# 780-00012-P3_Sch_M2_Focus_Drive.net
KiCad netlist of a schematic drawn in Altium Designer
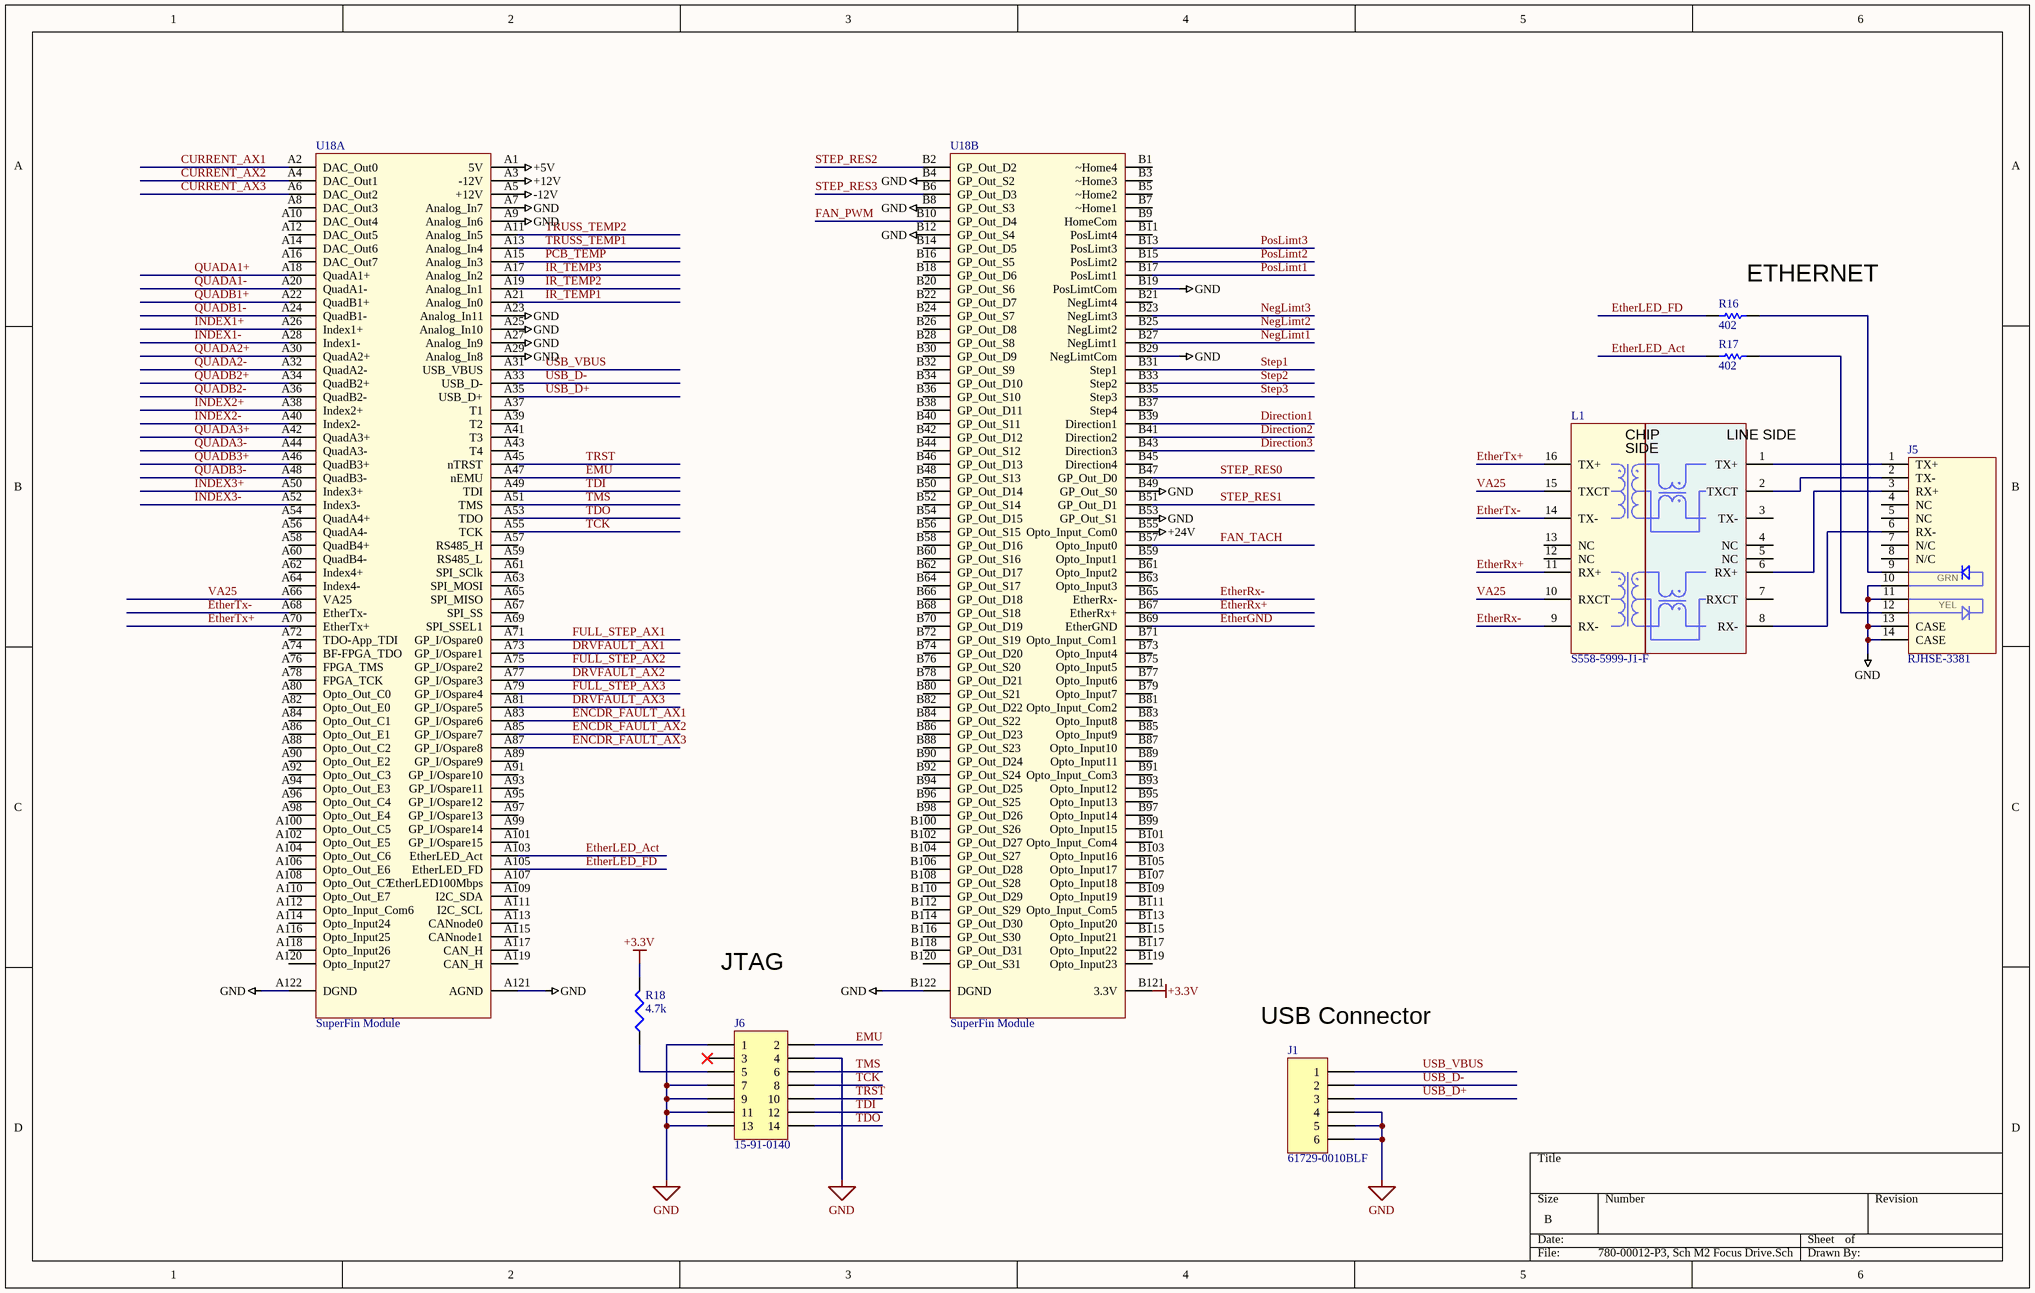
[diagram p0: 780-00012-P3, Sch M2 Focus Drive.SchDoc]

(export (version "E")
  (design (tool "Eeschema 10.0.6"))
  (components
    (comp (ref "J1")
      (value "61729-0010BLF")
      (footprint "USB Vertical PCB")
      (description "Header, 6-Pin")
      (fields (field (name "MANUFACTURER") "FCI"))
      (libsource (lib "Miscellaneous Connectors") (part "Header 6"))
    )
    (comp (ref "J5")
      (value "RJHSE-3381")
      (footprint "RJ45, VERT MOUNT, NO MAGNETICS")
      (description "Vertical PC mount, w/o magnetics")
      (libsource (lib "Richs Schematic Components") (part "CONN RJ-45 w/o magnetics"))
    )
    (comp (ref "J6")
      (value "15-91-0140")
      (footprint "HDR2X7")
      (description "Header, 7-Pin, Dual row")
      (fields (field (name "MANUFACTURER") "Molex/Waldom"))
      (libsource (lib "Miscellaneous Connectors") (part "Header 7X2"))
    )
    (comp (ref "L1")
      (value "S558-5999-J1-F")
      (footprint "10/100BT Magetics module")
      (description "10/100BT Magnetics Module")
      (libsource (lib "Richs Schematic Components") (part "Ethernet Magnetics module"))
    )
    (comp (ref "R16")
      (value "402")
      (footprint "SMD_0805")
      (description "Resistor 0805")
      (fields (field (name "MANUFACTURER") "Vishay/Dale") (field (name "Comment") "Res 0805"))
      (libsource (lib "Richs Schematic Components") (part "Res SMD"))
    )
    (comp (ref "R17")
      (value "402")
      (footprint "SMD_0805")
      (description "Resistor 0805")
      (fields (field (name "MANUFACTURER") "Vishay/Dale") (field (name "Comment") "Res 0805"))
      (libsource (lib "Richs Schematic Components") (part "Res SMD"))
    )
    (comp (ref "R18")
      (value "4.7k")
      (footprint "2012[0805]")
      (description "Resistor")
      (fields (field (name "MANUFACTURER") "Dale/Vishay"))
      (libsource (lib "Miscellaneous Devices") (part "Res3"))
    )
    (comp (ref "U18")
      (value "SuperFin Module")
      (footprint "SuperFin Footprint")
      (libsource (lib "Richs Schematic Components") (part "SuperFin Module"))
    )
  )
  (nets
    (net (code "1") (name "+3.3V") (class "Default")
      (node (ref "R18") (pin "2") (pinfunction "2_2") (pintype "passive"))
      (node (ref "U18") (pin "B121") (pinfunction "3.3V_B121") (pintype "passive"))
    )
    (net (code "2") (name "+5V") (class "Default")
      (node (ref "U18") (pin "A1") (pinfunction "5V_A1") (pintype "passive"))
    )
    (net (code "3") (name "+12V") (class "Default")
      (node (ref "U18") (pin "A3") (pinfunction "-12V_A3") (pintype "passive"))
    )
    (net (code "4") (name "+24V") (class "Default")
      (node (ref "U18") (pin "B55") (pinfunction "Opto_Input_Com0_B55") (pintype "passive"))
    )
    (net (code "5") (name "-12V") (class "Default")
      (node (ref "U18") (pin "A5") (pinfunction "+12V_A5") (pintype "passive"))
    )
    (net (code "6") (name "/CURRENT_AX1") (class "Default")
      (node (ref "U18") (pin "A2") (pinfunction "DAC_Out0_A2") (pintype "passive"))
    )
    (net (code "7") (name "/CURRENT_AX2") (class "Default")
      (node (ref "U18") (pin "A4") (pinfunction "DAC_Out1_A4") (pintype "passive"))
    )
    (net (code "8") (name "/CURRENT_AX3") (class "Default")
      (node (ref "U18") (pin "A6") (pinfunction "DAC_Out2_A6") (pintype "passive"))
    )
    (net (code "9") (name "/DRVFAULT_AX1") (class "Default")
      (node (ref "U18") (pin "A73") (pinfunction "GP_I/Ospare1_A73") (pintype "passive"))
    )
    (net (code "10") (name "/DRVFAULT_AX2") (class "Default")
      (node (ref "U18") (pin "A77") (pinfunction "GP_I/Ospare3_A77") (pintype "passive"))
    )
    (net (code "11") (name "/DRVFAULT_AX3") (class "Default")
      (node (ref "U18") (pin "A81") (pinfunction "GP_I/Ospare5_A81") (pintype "passive"))
    )
    (net (code "12") (name "/Direction1") (class "Default")
      (node (ref "U18") (pin "B39") (pinfunction "Direction1_B39") (pintype "passive"))
    )
    (net (code "13") (name "/Direction2") (class "Default")
      (node (ref "U18") (pin "B41") (pinfunction "Direction2_B41") (pintype "passive"))
    )
    (net (code "14") (name "/Direction3") (class "Default")
      (node (ref "U18") (pin "B43") (pinfunction "Direction3_B43") (pintype "passive"))
    )
    (net (code "15") (name "/EMU") (class "Default")
      (node (ref "J6") (pin "2") (pinfunction "2_2") (pintype "passive"))
      (node (ref "U18") (pin "A47") (pinfunction "nEMU_A47") (pintype "passive"))
    )
    (net (code "16") (name "/ENCDR_FAULT_AX1") (class "Default")
      (node (ref "U18") (pin "A83") (pinfunction "GP_I/Ospare6_A83") (pintype "passive"))
    )
    (net (code "17") (name "/ENCDR_FAULT_AX2") (class "Default")
      (node (ref "U18") (pin "A85") (pinfunction "GP_I/Ospare7_A85") (pintype "passive"))
    )
    (net (code "18") (name "/ENCDR_FAULT_AX3") (class "Default")
      (node (ref "U18") (pin "A87") (pinfunction "GP_I/Ospare8_A87") (pintype "passive"))
    )
    (net (code "19") (name "/EtherGND") (class "Default")
      (node (ref "U18") (pin "B69") (pinfunction "EtherGND_B69") (pintype "passive"))
    )
    (net (code "20") (name "/EtherLED_Act") (class "Default")
      (node (ref "R17") (pin "1") (pinfunction "1_1") (pintype "passive"))
      (node (ref "U18") (pin "A103") (pinfunction "EtherLED_Act_A103") (pintype "passive"))
    )
    (net (code "21") (name "/EtherLED_FD") (class "Default")
      (node (ref "R16") (pin "1") (pinfunction "1_1") (pintype "passive"))
      (node (ref "U18") (pin "A105") (pinfunction "EtherLED_FD_A105") (pintype "passive"))
    )
    (net (code "22") (name "/EtherRx+") (class "Default")
      (node (ref "L1") (pin "11") (pinfunction "RX+_11") (pintype "passive"))
      (node (ref "U18") (pin "B67") (pinfunction "EtherRx+_B67") (pintype "passive"))
    )
    (net (code "23") (name "/EtherRx-") (class "Default")
      (node (ref "L1") (pin "9") (pinfunction "RX-_9") (pintype "passive"))
      (node (ref "U18") (pin "B65") (pinfunction "EtherRx-_B65") (pintype "passive"))
    )
    (net (code "24") (name "/EtherTx+") (class "Default")
      (node (ref "L1") (pin "16") (pinfunction "TX+_16") (pintype "passive"))
      (node (ref "U18") (pin "A70") (pinfunction "EtherTx+_A70") (pintype "passive"))
    )
    (net (code "25") (name "/EtherTx-") (class "Default")
      (node (ref "L1") (pin "14") (pinfunction "TX-_14") (pintype "passive"))
      (node (ref "U18") (pin "A68") (pinfunction "EtherTx-_A68") (pintype "passive"))
    )
    (net (code "26") (name "/FAN_PWM") (class "Default")
      (node (ref "U18") (pin "B10") (pinfunction "GP_Out_D4_B10") (pintype "passive"))
    )
    (net (code "27") (name "/FAN_TACH") (class "Default")
      (node (ref "U18") (pin "B57") (pinfunction "Opto_Input0_B57") (pintype "passive"))
    )
    (net (code "28") (name "/FULL_STEP_AX1") (class "Default")
      (node (ref "U18") (pin "A71") (pinfunction "GP_I/Ospare0_A71") (pintype "passive"))
    )
    (net (code "29") (name "/FULL_STEP_AX2") (class "Default")
      (node (ref "U18") (pin "A75") (pinfunction "GP_I/Ospare2_A75") (pintype "passive"))
    )
    (net (code "30") (name "/FULL_STEP_AX3") (class "Default")
      (node (ref "U18") (pin "A79") (pinfunction "GP_I/Ospare4_A79") (pintype "passive"))
    )
    (net (code "31") (name "/INDEX1+") (class "Default")
      (node (ref "U18") (pin "A26") (pinfunction "Index1+_A26") (pintype "passive"))
    )
    (net (code "32") (name "/INDEX1-") (class "Default")
      (node (ref "U18") (pin "A28") (pinfunction "Index1-_A28") (pintype "passive"))
    )
    (net (code "33") (name "/INDEX2+") (class "Default")
      (node (ref "U18") (pin "A38") (pinfunction "Index2+_A38") (pintype "passive"))
    )
    (net (code "34") (name "/INDEX2-") (class "Default")
      (node (ref "U18") (pin "A40") (pinfunction "Index2-_A40") (pintype "passive"))
    )
    (net (code "35") (name "/INDEX3+") (class "Default")
      (node (ref "U18") (pin "A50") (pinfunction "Index3+_A50") (pintype "passive"))
    )
    (net (code "36") (name "/INDEX3-") (class "Default")
      (node (ref "U18") (pin "A52") (pinfunction "Index3-_A52") (pintype "passive"))
    )
    (net (code "37") (name "/IR_TEMP1") (class "Default")
      (node (ref "U18") (pin "A21") (pinfunction "Analog_In0_A21") (pintype "passive"))
    )
    (net (code "38") (name "/IR_TEMP2") (class "Default")
      (node (ref "U18") (pin "A19") (pinfunction "Analog_In1_A19") (pintype "passive"))
    )
    (net (code "39") (name "/IR_TEMP3") (class "Default")
      (node (ref "U18") (pin "A17") (pinfunction "Analog_In2_A17") (pintype "passive"))
    )
    (net (code "40") (name "/NegLimt1") (class "Default")
      (node (ref "U18") (pin "B27") (pinfunction "NegLimt1_B27") (pintype "passive"))
    )
    (net (code "41") (name "/NegLimt2") (class "Default")
      (node (ref "U18") (pin "B25") (pinfunction "NegLimt2_B25") (pintype "passive"))
    )
    (net (code "42") (name "/NegLimt3") (class "Default")
      (node (ref "U18") (pin "B23") (pinfunction "NegLimt3_B23") (pintype "passive"))
    )
    (net (code "43") (name "/PCB_TEMP") (class "Default")
      (node (ref "U18") (pin "A15") (pinfunction "Analog_In3_A15") (pintype "passive"))
    )
    (net (code "44") (name "/PosLimt1") (class "Default")
      (node (ref "U18") (pin "B17") (pinfunction "PosLimt1_B17") (pintype "passive"))
    )
    (net (code "45") (name "/PosLimt2") (class "Default")
      (node (ref "U18") (pin "B15") (pinfunction "PosLimt2_B15") (pintype "passive"))
    )
    (net (code "46") (name "/PosLimt3") (class "Default")
      (node (ref "U18") (pin "B13") (pinfunction "PosLimt3_B13") (pintype "passive"))
    )
    (net (code "47") (name "/QUADA1+") (class "Default")
      (node (ref "U18") (pin "A18") (pinfunction "QuadA1+_A18") (pintype "passive"))
    )
    (net (code "48") (name "/QUADA1-") (class "Default")
      (node (ref "U18") (pin "A20") (pinfunction "QuadA1-_A20") (pintype "passive"))
    )
    (net (code "49") (name "/QUADA2+") (class "Default")
      (node (ref "U18") (pin "A30") (pinfunction "QuadA2+_A30") (pintype "passive"))
    )
    (net (code "50") (name "/QUADA2-") (class "Default")
      (node (ref "U18") (pin "A32") (pinfunction "QuadA2-_A32") (pintype "passive"))
    )
    (net (code "51") (name "/QUADA3+") (class "Default")
      (node (ref "U18") (pin "A42") (pinfunction "QuadA3+_A42") (pintype "passive"))
    )
    (net (code "52") (name "/QUADA3-") (class "Default")
      (node (ref "U18") (pin "A44") (pinfunction "QuadA3-_A44") (pintype "passive"))
    )
    (net (code "53") (name "/QUADB1+") (class "Default")
      (node (ref "U18") (pin "A22") (pinfunction "QuadB1+_A22") (pintype "passive"))
    )
    (net (code "54") (name "/QUADB1-") (class "Default")
      (node (ref "U18") (pin "A24") (pinfunction "QuadB1-_A24") (pintype "passive"))
    )
    (net (code "55") (name "/QUADB2+") (class "Default")
      (node (ref "U18") (pin "A34") (pinfunction "QuadB2+_A34") (pintype "passive"))
    )
    (net (code "56") (name "/QUADB2-") (class "Default")
      (node (ref "U18") (pin "A36") (pinfunction "QuadB2-_A36") (pintype "passive"))
    )
    (net (code "57") (name "/QUADB3+") (class "Default")
      (node (ref "U18") (pin "A46") (pinfunction "QuadB3+_A46") (pintype "passive"))
    )
    (net (code "58") (name "/QUADB3-") (class "Default")
      (node (ref "U18") (pin "A48") (pinfunction "QuadB3-_A48") (pintype "passive"))
    )
    (net (code "59") (name "/STEP_RES0") (class "Default")
      (node (ref "U18") (pin "B47") (pinfunction "GP_Out_D0_B47") (pintype "passive"))
    )
    (net (code "60") (name "/STEP_RES1") (class "Default")
      (node (ref "U18") (pin "B51") (pinfunction "GP_Out_D1_B51") (pintype "passive"))
    )
    (net (code "61") (name "/STEP_RES2") (class "Default")
      (node (ref "U18") (pin "B2") (pinfunction "GP_Out_D2_B2") (pintype "passive"))
    )
    (net (code "62") (name "/STEP_RES3") (class "Default")
      (node (ref "U18") (pin "B6") (pinfunction "GP_Out_D3_B6") (pintype "passive"))
    )
    (net (code "63") (name "/Step1") (class "Default")
      (node (ref "U18") (pin "B31") (pinfunction "Step1_B31") (pintype "passive"))
    )
    (net (code "64") (name "/Step2") (class "Default")
      (node (ref "U18") (pin "B33") (pinfunction "Step2_B33") (pintype "passive"))
    )
    (net (code "65") (name "/Step3") (class "Default")
      (node (ref "U18") (pin "B35") (pinfunction "Step3_B35") (pintype "passive"))
    )
    (net (code "66") (name "/TCK") (class "Default")
      (node (ref "J6") (pin "8") (pinfunction "8_8") (pintype "passive"))
      (node (ref "U18") (pin "A55") (pinfunction "TCK_A55") (pintype "passive"))
    )
    (net (code "67") (name "/TDI") (class "Default")
      (node (ref "J6") (pin "12") (pinfunction "12_12") (pintype "passive"))
      (node (ref "U18") (pin "A49") (pinfunction "TDI_A49") (pintype "passive"))
    )
    (net (code "68") (name "/TDO") (class "Default")
      (node (ref "J6") (pin "14") (pinfunction "14_14") (pintype "passive"))
      (node (ref "U18") (pin "A53") (pinfunction "TDO_A53") (pintype "passive"))
    )
    (net (code "69") (name "/TMS") (class "Default")
      (node (ref "J6") (pin "6") (pinfunction "6_6") (pintype "passive"))
      (node (ref "U18") (pin "A51") (pinfunction "TMS_A51") (pintype "passive"))
    )
    (net (code "70") (name "/TRST") (class "Default")
      (node (ref "J6") (pin "10") (pinfunction "10_10") (pintype "passive"))
      (node (ref "U18") (pin "A45") (pinfunction "nTRST_A45") (pintype "passive"))
    )
    (net (code "71") (name "/TRUSS_TEMP1") (class "Default")
      (node (ref "U18") (pin "A13") (pinfunction "Analog_In4_A13") (pintype "passive"))
    )
    (net (code "72") (name "/TRUSS_TEMP2") (class "Default")
      (node (ref "U18") (pin "A11") (pinfunction "Analog_In5_A11") (pintype "passive"))
    )
    (net (code "73") (name "/USB_D+") (class "Default")
      (node (ref "J1") (pin "3") (pinfunction "3_3") (pintype "passive"))
      (node (ref "U18") (pin "A35") (pinfunction "USB_D+_A35") (pintype "passive"))
    )
    (net (code "74") (name "/USB_D-") (class "Default")
      (node (ref "J1") (pin "2") (pinfunction "2_2") (pintype "passive"))
      (node (ref "U18") (pin "A33") (pinfunction "USB_D-_A33") (pintype "passive"))
    )
    (net (code "75") (name "/USB_VBUS") (class "Default")
      (node (ref "J1") (pin "1") (pinfunction "1_1") (pintype "passive"))
      (node (ref "U18") (pin "A31") (pinfunction "USB_VBUS_A31") (pintype "passive"))
    )
    (net (code "76") (name "/VA25") (class "Default")
      (node (ref "L1") (pin "10") (pinfunction "RXCT_10") (pintype "passive"))
      (node (ref "L1") (pin "15") (pinfunction "TXCT_15") (pintype "passive"))
      (node (ref "U18") (pin "A66") (pinfunction "VA25_A66") (pintype "passive"))
    )
    (net (code "77") (name "GND") (class "Default")
      (node (ref "J1") (pin "4") (pinfunction "4_4") (pintype "passive"))
      (node (ref "J1") (pin "5") (pinfunction "5_5") (pintype "passive"))
      (node (ref "J1") (pin "6") (pinfunction "6_6") (pintype "passive"))
      (node (ref "J5") (pin "10") (pinfunction "GRN-Cathode_10") (pintype "passive"))
      (node (ref "J5") (pin "11") (pinfunction "YEL-Cathode_11") (pintype "passive"))
      (node (ref "J5") (pin "13") (pinfunction "CASE_13") (pintype "passive"))
      (node (ref "J5") (pin "14") (pinfunction "CASE_14") (pintype "passive"))
      (node (ref "J6") (pin "1") (pinfunction "1_1") (pintype "passive"))
      (node (ref "J6") (pin "11") (pinfunction "11_11") (pintype "passive"))
      (node (ref "J6") (pin "13") (pinfunction "13_13") (pintype "passive"))
      (node (ref "J6") (pin "4") (pinfunction "4_4") (pintype "passive"))
      (node (ref "J6") (pin "7") (pinfunction "7_7") (pintype "passive"))
      (node (ref "J6") (pin "9") (pinfunction "9_9") (pintype "passive"))
      (node (ref "U18") (pin "A121") (pinfunction "AGND_A121") (pintype "passive"))
      (node (ref "U18") (pin "A122") (pinfunction "DGND_A122") (pintype "passive"))
      (node (ref "U18") (pin "A23") (pinfunction "Analog_In11_A23") (pintype "passive"))
      (node (ref "U18") (pin "A25") (pinfunction "Analog_In10_A25") (pintype "passive"))
      (node (ref "U18") (pin "A27") (pinfunction "Analog_In9_A27") (pintype "passive"))
      (node (ref "U18") (pin "A29") (pinfunction "Analog_In8_A29") (pintype "passive"))
      (node (ref "U18") (pin "A7") (pinfunction "Analog_In7_A7") (pintype "passive"))
      (node (ref "U18") (pin "A9") (pinfunction "Analog_In6_A9") (pintype "passive"))
      (node (ref "U18") (pin "B12") (pinfunction "GP_Out_S4_B12") (pintype "passive"))
      (node (ref "U18") (pin "B122") (pinfunction "DGND_B122") (pintype "passive"))
      (node (ref "U18") (pin "B19") (pinfunction "PosLimtCom_B19") (pintype "passive"))
      (node (ref "U18") (pin "B29") (pinfunction "NegLimtCom_B29") (pintype "passive"))
      (node (ref "U18") (pin "B4") (pinfunction "GP_Out_S2_B4") (pintype "passive"))
      (node (ref "U18") (pin "B49") (pinfunction "GP_Out_S0_B49") (pintype "passive"))
      (node (ref "U18") (pin "B53") (pinfunction "GP_Out_S1_B53") (pintype "passive"))
      (node (ref "U18") (pin "B8") (pinfunction "GP_Out_S3_B8") (pintype "passive"))
    )
    (net (code "78") (name "Net-(J5-GRN-Anode)") (class "Default")
      (node (ref "J5") (pin "9") (pinfunction "GRN-Anode_9") (pintype "passive"))
      (node (ref "R16") (pin "2") (pinfunction "2_2") (pintype "passive"))
    )
    (net (code "79") (name "Net-(J5-RX+)") (class "Default")
      (node (ref "J5") (pin "3") (pinfunction "RX+_3") (pintype "passive"))
      (node (ref "L1") (pin "6") (pinfunction "RX+_6") (pintype "passive"))
    )
    (net (code "80") (name "Net-(J5-RX-)") (class "Default")
      (node (ref "J5") (pin "6") (pinfunction "RX-_6") (pintype "passive"))
      (node (ref "L1") (pin "8") (pinfunction "RX-_8") (pintype "passive"))
    )
    (net (code "81") (name "Net-(J5-TX+)") (class "Default")
      (node (ref "J5") (pin "1") (pinfunction "TX+_1") (pintype "passive"))
      (node (ref "L1") (pin "1") (pinfunction "TX+_1") (pintype "passive"))
    )
    (net (code "82") (name "Net-(J5-TX-)") (class "Default")
      (node (ref "J5") (pin "2") (pinfunction "TX-_2") (pintype "passive"))
      (node (ref "L1") (pin "2") (pinfunction "TXCT_2") (pintype "passive"))
    )
    (net (code "83") (name "Net-(J5-YEL-Anode)") (class "Default")
      (node (ref "J5") (pin "12") (pinfunction "YEL-Anode_12") (pintype "passive"))
      (node (ref "R17") (pin "2") (pinfunction "2_2") (pintype "passive"))
    )
    (net (code "84") (name "Net-(J6-Pad5)") (class "Default")
      (node (ref "J6") (pin "5") (pinfunction "5_5") (pintype "passive"))
      (node (ref "R18") (pin "1") (pinfunction "1_1") (pintype "passive"))
    )
    (net (code "85") (name "unconnected-(J5-NC-Pad4)") (class "Default")
      (node (ref "J5") (pin "4") (pinfunction "NC_4") (pintype "passive"))
    )
    (net (code "86") (name "unconnected-(J5-NC-Pad5)") (class "Default")
      (node (ref "J5") (pin "5") (pinfunction "NC_5") (pintype "passive"))
    )
    (net (code "87") (name "unconnected-(J5-N{slash}C-Pad7)") (class "Default")
      (node (ref "J5") (pin "7") (pinfunction "N/C_7") (pintype "passive"))
    )
    (net (code "88") (name "unconnected-(J5-N{slash}C-Pad8)") (class "Default")
      (node (ref "J5") (pin "8") (pinfunction "N/C_8") (pintype "passive"))
    )
    (net (code "89") (name "unconnected-(J6-Pad3)") (class "Default")
      (node (ref "J6") (pin "3") (pinfunction "3_3") (pintype "passive+no_connect"))
    )
    (net (code "90") (name "unconnected-(L1-NC-Pad4)") (class "Default")
      (node (ref "L1") (pin "4") (pinfunction "NC_4") (pintype "passive"))
    )
    (net (code "91") (name "unconnected-(L1-NC-Pad5)") (class "Default")
      (node (ref "L1") (pin "5") (pinfunction "NC_5") (pintype "passive"))
    )
    (net (code "92") (name "unconnected-(L1-NC-Pad12)") (class "Default")
      (node (ref "L1") (pin "12") (pinfunction "NC_12") (pintype "passive"))
    )
    (net (code "93") (name "unconnected-(L1-NC-Pad13)") (class "Default")
      (node (ref "L1") (pin "13") (pinfunction "NC_13") (pintype "passive"))
    )
    (net (code "94") (name "unconnected-(L1-RXCT-Pad7)") (class "Default")
      (node (ref "L1") (pin "7") (pinfunction "RXCT_7") (pintype "passive"))
    )
    (net (code "95") (name "unconnected-(L1-TX--Pad3)") (class "Default")
      (node (ref "L1") (pin "3") (pinfunction "TX-_3") (pintype "passive"))
    )
    (net (code "96") (name "unconnected-(U18A-BF-FPGA_TDO-PadA74)") (class "Default")
      (node (ref "U18") (pin "A74") (pinfunction "BF-FPGA_TDO_A74") (pintype "passive"))
    )
    (net (code "97") (name "unconnected-(U18A-CAN_H-PadA117)") (class "Default")
      (node (ref "U18") (pin "A117") (pinfunction "CAN_H_A117") (pintype "passive"))
    )
    (net (code "98") (name "unconnected-(U18A-CAN_H-PadA119)") (class "Default")
      (node (ref "U18") (pin "A119") (pinfunction "CAN_H_A119") (pintype "passive"))
    )
    (net (code "99") (name "unconnected-(U18A-CANnode0-PadA113)") (class "Default")
      (node (ref "U18") (pin "A113") (pinfunction "CANnode0_A113") (pintype "passive"))
    )
    (net (code "100") (name "unconnected-(U18A-CANnode1-PadA115)") (class "Default")
      (node (ref "U18") (pin "A115") (pinfunction "CANnode1_A115") (pintype "passive"))
    )
    (net (code "101") (name "unconnected-(U18A-DAC_Out3-PadA8)") (class "Default")
      (node (ref "U18") (pin "A8") (pinfunction "DAC_Out3_A8") (pintype "passive"))
    )
    (net (code "102") (name "unconnected-(U18A-DAC_Out4-PadA10)") (class "Default")
      (node (ref "U18") (pin "A10") (pinfunction "DAC_Out4_A10") (pintype "passive"))
    )
    (net (code "103") (name "unconnected-(U18A-DAC_Out5-PadA12)") (class "Default")
      (node (ref "U18") (pin "A12") (pinfunction "DAC_Out5_A12") (pintype "passive"))
    )
    (net (code "104") (name "unconnected-(U18A-DAC_Out6-PadA14)") (class "Default")
      (node (ref "U18") (pin "A14") (pinfunction "DAC_Out6_A14") (pintype "passive"))
    )
    (net (code "105") (name "unconnected-(U18A-DAC_Out7-PadA16)") (class "Default")
      (node (ref "U18") (pin "A16") (pinfunction "DAC_Out7_A16") (pintype "passive"))
    )
    (net (code "106") (name "unconnected-(U18A-EtherLED100Mbps-PadA107)") (class "Default")
      (node (ref "U18") (pin "A107") (pinfunction "EtherLED100Mbps_A107") (pintype "passive"))
    )
    (net (code "107") (name "unconnected-(U18A-FPGA_TCK-PadA78)") (class "Default")
      (node (ref "U18") (pin "A78") (pinfunction "FPGA_TCK_A78") (pintype "passive"))
    )
    (net (code "108") (name "unconnected-(U18A-FPGA_TMS-PadA76)") (class "Default")
      (node (ref "U18") (pin "A76") (pinfunction "FPGA_TMS_A76") (pintype "passive"))
    )
    (net (code "109") (name "unconnected-(U18A-GP_I{slash}Ospare9-PadA89)") (class "Default")
      (node (ref "U18") (pin "A89") (pinfunction "GP_I/Ospare9_A89") (pintype "passive"))
    )
    (net (code "110") (name "unconnected-(U18A-GP_I{slash}Ospare10-PadA91)") (class "Default")
      (node (ref "U18") (pin "A91") (pinfunction "GP_I/Ospare10_A91") (pintype "passive"))
    )
    (net (code "111") (name "unconnected-(U18A-GP_I{slash}Ospare11-PadA93)") (class "Default")
      (node (ref "U18") (pin "A93") (pinfunction "GP_I/Ospare11_A93") (pintype "passive"))
    )
    (net (code "112") (name "unconnected-(U18A-GP_I{slash}Ospare12-PadA95)") (class "Default")
      (node (ref "U18") (pin "A95") (pinfunction "GP_I/Ospare12_A95") (pintype "passive"))
    )
    (net (code "113") (name "unconnected-(U18A-GP_I{slash}Ospare13-PadA97)") (class "Default")
      (node (ref "U18") (pin "A97") (pinfunction "GP_I/Ospare13_A97") (pintype "passive"))
    )
    (net (code "114") (name "unconnected-(U18A-GP_I{slash}Ospare14-PadA99)") (class "Default")
      (node (ref "U18") (pin "A99") (pinfunction "GP_I/Ospare14_A99") (pintype "passive"))
    )
    (net (code "115") (name "unconnected-(U18A-GP_I{slash}Ospare15-PadA101)") (class "Default")
      (node (ref "U18") (pin "A101") (pinfunction "GP_I/Ospare15_A101") (pintype "passive"))
    )
    (net (code "116") (name "unconnected-(U18A-I2C_SCL-PadA111)") (class "Default")
      (node (ref "U18") (pin "A111") (pinfunction "I2C_SCL_A111") (pintype "passive"))
    )
    (net (code "117") (name "unconnected-(U18A-I2C_SDA-PadA109)") (class "Default")
      (node (ref "U18") (pin "A109") (pinfunction "I2C_SDA_A109") (pintype "passive"))
    )
    (net (code "118") (name "unconnected-(U18A-Index4+-PadA62)") (class "Default")
      (node (ref "U18") (pin "A62") (pinfunction "Index4+_A62") (pintype "passive"))
    )
    (net (code "119") (name "unconnected-(U18A-Index4--PadA64)") (class "Default")
      (node (ref "U18") (pin "A64") (pinfunction "Index4-_A64") (pintype "passive"))
    )
    (net (code "120") (name "unconnected-(U18A-Opto_Input24-PadA114)") (class "Default")
      (node (ref "U18") (pin "A114") (pinfunction "Opto_Input24_A114") (pintype "passive"))
    )
    (net (code "121") (name "unconnected-(U18A-Opto_Input25-PadA116)") (class "Default")
      (node (ref "U18") (pin "A116") (pinfunction "Opto_Input25_A116") (pintype "passive"))
    )
    (net (code "122") (name "unconnected-(U18A-Opto_Input26-PadA118)") (class "Default")
      (node (ref "U18") (pin "A118") (pinfunction "Opto_Input26_A118") (pintype "passive"))
    )
    (net (code "123") (name "unconnected-(U18A-Opto_Input27-PadA120)") (class "Default")
      (node (ref "U18") (pin "A120") (pinfunction "Opto_Input27_A120") (pintype "passive"))
    )
    (net (code "124") (name "unconnected-(U18A-Opto_Input_Com6-PadA112)") (class "Default")
      (node (ref "U18") (pin "A112") (pinfunction "Opto_Input_Com6_A112") (pintype "passive"))
    )
    (net (code "125") (name "unconnected-(U18A-Opto_Out_C0-PadA80)") (class "Default")
      (node (ref "U18") (pin "A80") (pinfunction "Opto_Out_C0_A80") (pintype "passive"))
    )
    (net (code "126") (name "unconnected-(U18A-Opto_Out_C1-PadA84)") (class "Default")
      (node (ref "U18") (pin "A84") (pinfunction "Opto_Out_C1_A84") (pintype "passive"))
    )
    (net (code "127") (name "unconnected-(U18A-Opto_Out_C2-PadA88)") (class "Default")
      (node (ref "U18") (pin "A88") (pinfunction "Opto_Out_C2_A88") (pintype "passive"))
    )
    (net (code "128") (name "unconnected-(U18A-Opto_Out_C3-PadA92)") (class "Default")
      (node (ref "U18") (pin "A92") (pinfunction "Opto_Out_C3_A92") (pintype "passive"))
    )
    (net (code "129") (name "unconnected-(U18A-Opto_Out_C4-PadA96)") (class "Default")
      (node (ref "U18") (pin "A96") (pinfunction "Opto_Out_C4_A96") (pintype "passive"))
    )
    (net (code "130") (name "unconnected-(U18A-Opto_Out_C5-PadA100)") (class "Default")
      (node (ref "U18") (pin "A100") (pinfunction "Opto_Out_C5_A100") (pintype "passive"))
    )
    (net (code "131") (name "unconnected-(U18A-Opto_Out_C6-PadA104)") (class "Default")
      (node (ref "U18") (pin "A104") (pinfunction "Opto_Out_C6_A104") (pintype "passive"))
    )
    (net (code "132") (name "unconnected-(U18A-Opto_Out_C7-PadA108)") (class "Default")
      (node (ref "U18") (pin "A108") (pinfunction "Opto_Out_C7_A108") (pintype "passive"))
    )
    (net (code "133") (name "unconnected-(U18A-Opto_Out_E0-PadA82)") (class "Default")
      (node (ref "U18") (pin "A82") (pinfunction "Opto_Out_E0_A82") (pintype "passive"))
    )
    (net (code "134") (name "unconnected-(U18A-Opto_Out_E1-PadA86)") (class "Default")
      (node (ref "U18") (pin "A86") (pinfunction "Opto_Out_E1_A86") (pintype "passive"))
    )
    (net (code "135") (name "unconnected-(U18A-Opto_Out_E2-PadA90)") (class "Default")
      (node (ref "U18") (pin "A90") (pinfunction "Opto_Out_E2_A90") (pintype "passive"))
    )
    (net (code "136") (name "unconnected-(U18A-Opto_Out_E3-PadA94)") (class "Default")
      (node (ref "U18") (pin "A94") (pinfunction "Opto_Out_E3_A94") (pintype "passive"))
    )
    (net (code "137") (name "unconnected-(U18A-Opto_Out_E4-PadA98)") (class "Default")
      (node (ref "U18") (pin "A98") (pinfunction "Opto_Out_E4_A98") (pintype "passive"))
    )
    (net (code "138") (name "unconnected-(U18A-Opto_Out_E5-PadA102)") (class "Default")
      (node (ref "U18") (pin "A102") (pinfunction "Opto_Out_E5_A102") (pintype "passive"))
    )
    (net (code "139") (name "unconnected-(U18A-Opto_Out_E6-PadA106)") (class "Default")
      (node (ref "U18") (pin "A106") (pinfunction "Opto_Out_E6_A106") (pintype "passive"))
    )
    (net (code "140") (name "unconnected-(U18A-Opto_Out_E7-PadA110)") (class "Default")
      (node (ref "U18") (pin "A110") (pinfunction "Opto_Out_E7_A110") (pintype "passive"))
    )
    (net (code "141") (name "unconnected-(U18A-QuadA4+-PadA54)") (class "Default")
      (node (ref "U18") (pin "A54") (pinfunction "QuadA4+_A54") (pintype "passive"))
    )
    (net (code "142") (name "unconnected-(U18A-QuadA4--PadA56)") (class "Default")
      (node (ref "U18") (pin "A56") (pinfunction "QuadA4-_A56") (pintype "passive"))
    )
    (net (code "143") (name "unconnected-(U18A-QuadB4+-PadA58)") (class "Default")
      (node (ref "U18") (pin "A58") (pinfunction "QuadB4+_A58") (pintype "passive"))
    )
    (net (code "144") (name "unconnected-(U18A-QuadB4--PadA60)") (class "Default")
      (node (ref "U18") (pin "A60") (pinfunction "QuadB4-_A60") (pintype "passive"))
    )
    (net (code "145") (name "unconnected-(U18A-RS485_H-PadA57)") (class "Default")
      (node (ref "U18") (pin "A57") (pinfunction "RS485_H_A57") (pintype "passive"))
    )
    (net (code "146") (name "unconnected-(U18A-RS485_L-PadA59)") (class "Default")
      (node (ref "U18") (pin "A59") (pinfunction "RS485_L_A59") (pintype "passive"))
    )
    (net (code "147") (name "unconnected-(U18A-SPI_MISO-PadA65)") (class "Default")
      (node (ref "U18") (pin "A65") (pinfunction "SPI_MISO_A65") (pintype "passive"))
    )
    (net (code "148") (name "unconnected-(U18A-SPI_MOSI-PadA63)") (class "Default")
      (node (ref "U18") (pin "A63") (pinfunction "SPI_MOSI_A63") (pintype "passive"))
    )
    (net (code "149") (name "unconnected-(U18A-SPI_SClk-PadA61)") (class "Default")
      (node (ref "U18") (pin "A61") (pinfunction "SPI_SClk_A61") (pintype "passive"))
    )
    (net (code "150") (name "unconnected-(U18A-SPI_SS-PadA67)") (class "Default")
      (node (ref "U18") (pin "A67") (pinfunction "SPI_SS_A67") (pintype "passive"))
    )
    (net (code "151") (name "unconnected-(U18A-SPI_SSEL1-PadA69)") (class "Default")
      (node (ref "U18") (pin "A69") (pinfunction "SPI_SSEL1_A69") (pintype "passive"))
    )
    (net (code "152") (name "unconnected-(U18A-T1-PadA37)") (class "Default")
      (node (ref "U18") (pin "A37") (pinfunction "T1_A37") (pintype "passive"))
    )
    (net (code "153") (name "unconnected-(U18A-T2-PadA39)") (class "Default")
      (node (ref "U18") (pin "A39") (pinfunction "T2_A39") (pintype "passive"))
    )
    (net (code "154") (name "unconnected-(U18A-T3-PadA41)") (class "Default")
      (node (ref "U18") (pin "A41") (pinfunction "T3_A41") (pintype "passive"))
    )
    (net (code "155") (name "unconnected-(U18A-T4-PadA43)") (class "Default")
      (node (ref "U18") (pin "A43") (pinfunction "T4_A43") (pintype "passive"))
    )
    (net (code "156") (name "unconnected-(U18A-TDO-App_TDI-PadA72)") (class "Default")
      (node (ref "U18") (pin "A72") (pinfunction "TDO-App_TDI_A72") (pintype "passive"))
    )
    (net (code "157") (name "unconnected-(U18B-Direction4-PadB45)") (class "Default")
      (node (ref "U18") (pin "B45") (pinfunction "Direction4_B45") (pintype "passive"))
    )
    (net (code "158") (name "unconnected-(U18B-GP_Out_D5-PadB14)") (class "Default")
      (node (ref "U18") (pin "B14") (pinfunction "GP_Out_D5_B14") (pintype "passive"))
    )
    (net (code "159") (name "unconnected-(U18B-GP_Out_D6-PadB18)") (class "Default")
      (node (ref "U18") (pin "B18") (pinfunction "GP_Out_D6_B18") (pintype "passive"))
    )
    (net (code "160") (name "unconnected-(U18B-GP_Out_D7-PadB22)") (class "Default")
      (node (ref "U18") (pin "B22") (pinfunction "GP_Out_D7_B22") (pintype "passive"))
    )
    (net (code "161") (name "unconnected-(U18B-GP_Out_D8-PadB26)") (class "Default")
      (node (ref "U18") (pin "B26") (pinfunction "GP_Out_D8_B26") (pintype "passive"))
    )
    (net (code "162") (name "unconnected-(U18B-GP_Out_D9-PadB30)") (class "Default")
      (node (ref "U18") (pin "B30") (pinfunction "GP_Out_D9_B30") (pintype "passive"))
    )
    (net (code "163") (name "unconnected-(U18B-GP_Out_D10-PadB34)") (class "Default")
      (node (ref "U18") (pin "B34") (pinfunction "GP_Out_D10_B34") (pintype "passive"))
    )
    (net (code "164") (name "unconnected-(U18B-GP_Out_D11-PadB38)") (class "Default")
      (node (ref "U18") (pin "B38") (pinfunction "GP_Out_D11_B38") (pintype "passive"))
    )
    (net (code "165") (name "unconnected-(U18B-GP_Out_D12-PadB42)") (class "Default")
      (node (ref "U18") (pin "B42") (pinfunction "GP_Out_D12_B42") (pintype "passive"))
    )
    (net (code "166") (name "unconnected-(U18B-GP_Out_D13-PadB46)") (class "Default")
      (node (ref "U18") (pin "B46") (pinfunction "GP_Out_D13_B46") (pintype "passive"))
    )
    (net (code "167") (name "unconnected-(U18B-GP_Out_D14-PadB50)") (class "Default")
      (node (ref "U18") (pin "B50") (pinfunction "GP_Out_D14_B50") (pintype "passive"))
    )
    (net (code "168") (name "unconnected-(U18B-GP_Out_D15-PadB54)") (class "Default")
      (node (ref "U18") (pin "B54") (pinfunction "GP_Out_D15_B54") (pintype "passive"))
    )
    (net (code "169") (name "unconnected-(U18B-GP_Out_D16-PadB58)") (class "Default")
      (node (ref "U18") (pin "B58") (pinfunction "GP_Out_D16_B58") (pintype "passive"))
    )
    (net (code "170") (name "unconnected-(U18B-GP_Out_D17-PadB62)") (class "Default")
      (node (ref "U18") (pin "B62") (pinfunction "GP_Out_D17_B62") (pintype "passive"))
    )
    (net (code "171") (name "unconnected-(U18B-GP_Out_D18-PadB66)") (class "Default")
      (node (ref "U18") (pin "B66") (pinfunction "GP_Out_D18_B66") (pintype "passive"))
    )
    (net (code "172") (name "unconnected-(U18B-GP_Out_D19-PadB70)") (class "Default")
      (node (ref "U18") (pin "B70") (pinfunction "GP_Out_D19_B70") (pintype "passive"))
    )
    (net (code "173") (name "unconnected-(U18B-GP_Out_D20-PadB74)") (class "Default")
      (node (ref "U18") (pin "B74") (pinfunction "GP_Out_D20_B74") (pintype "passive"))
    )
    (net (code "174") (name "unconnected-(U18B-GP_Out_D21-PadB78)") (class "Default")
      (node (ref "U18") (pin "B78") (pinfunction "GP_Out_D21_B78") (pintype "passive"))
    )
    (net (code "175") (name "unconnected-(U18B-GP_Out_D22-PadB82)") (class "Default")
      (node (ref "U18") (pin "B82") (pinfunction "GP_Out_D22_B82") (pintype "passive"))
    )
    (net (code "176") (name "unconnected-(U18B-GP_Out_D23-PadB86)") (class "Default")
      (node (ref "U18") (pin "B86") (pinfunction "GP_Out_D23_B86") (pintype "passive"))
    )
    (net (code "177") (name "unconnected-(U18B-GP_Out_D24-PadB90)") (class "Default")
      (node (ref "U18") (pin "B90") (pinfunction "GP_Out_D24_B90") (pintype "passive"))
    )
    (net (code "178") (name "unconnected-(U18B-GP_Out_D25-PadB94)") (class "Default")
      (node (ref "U18") (pin "B94") (pinfunction "GP_Out_D25_B94") (pintype "passive"))
    )
    (net (code "179") (name "unconnected-(U18B-GP_Out_D26-PadB98)") (class "Default")
      (node (ref "U18") (pin "B98") (pinfunction "GP_Out_D26_B98") (pintype "passive"))
    )
    (net (code "180") (name "unconnected-(U18B-GP_Out_D27-PadB102)") (class "Default")
      (node (ref "U18") (pin "B102") (pinfunction "GP_Out_D27_B102") (pintype "passive"))
    )
    (net (code "181") (name "unconnected-(U18B-GP_Out_D28-PadB106)") (class "Default")
      (node (ref "U18") (pin "B106") (pinfunction "GP_Out_D28_B106") (pintype "passive"))
    )
    (net (code "182") (name "unconnected-(U18B-GP_Out_D29-PadB110)") (class "Default")
      (node (ref "U18") (pin "B110") (pinfunction "GP_Out_D29_B110") (pintype "passive"))
    )
    (net (code "183") (name "unconnected-(U18B-GP_Out_D30-PadB114)") (class "Default")
      (node (ref "U18") (pin "B114") (pinfunction "GP_Out_D30_B114") (pintype "passive"))
    )
    (net (code "184") (name "unconnected-(U18B-GP_Out_D31-PadB118)") (class "Default")
      (node (ref "U18") (pin "B118") (pinfunction "GP_Out_D31_B118") (pintype "passive"))
    )
    (net (code "185") (name "unconnected-(U18B-GP_Out_S5-PadB16)") (class "Default")
      (node (ref "U18") (pin "B16") (pinfunction "GP_Out_S5_B16") (pintype "passive"))
    )
    (net (code "186") (name "unconnected-(U18B-GP_Out_S6-PadB20)") (class "Default")
      (node (ref "U18") (pin "B20") (pinfunction "GP_Out_S6_B20") (pintype "passive"))
    )
    (net (code "187") (name "unconnected-(U18B-GP_Out_S7-PadB24)") (class "Default")
      (node (ref "U18") (pin "B24") (pinfunction "GP_Out_S7_B24") (pintype "passive"))
    )
    (net (code "188") (name "unconnected-(U18B-GP_Out_S8-PadB28)") (class "Default")
      (node (ref "U18") (pin "B28") (pinfunction "GP_Out_S8_B28") (pintype "passive"))
    )
    (net (code "189") (name "unconnected-(U18B-GP_Out_S9-PadB32)") (class "Default")
      (node (ref "U18") (pin "B32") (pinfunction "GP_Out_S9_B32") (pintype "passive"))
    )
    (net (code "190") (name "unconnected-(U18B-GP_Out_S10-PadB36)") (class "Default")
      (node (ref "U18") (pin "B36") (pinfunction "GP_Out_S10_B36") (pintype "passive"))
    )
    (net (code "191") (name "unconnected-(U18B-GP_Out_S11-PadB40)") (class "Default")
      (node (ref "U18") (pin "B40") (pinfunction "GP_Out_S11_B40") (pintype "passive"))
    )
    (net (code "192") (name "unconnected-(U18B-GP_Out_S12-PadB44)") (class "Default")
      (node (ref "U18") (pin "B44") (pinfunction "GP_Out_S12_B44") (pintype "passive"))
    )
    (net (code "193") (name "unconnected-(U18B-GP_Out_S13-PadB48)") (class "Default")
      (node (ref "U18") (pin "B48") (pinfunction "GP_Out_S13_B48") (pintype "passive"))
    )
    (net (code "194") (name "unconnected-(U18B-GP_Out_S14-PadB52)") (class "Default")
      (node (ref "U18") (pin "B52") (pinfunction "GP_Out_S14_B52") (pintype "passive"))
    )
    (net (code "195") (name "unconnected-(U18B-GP_Out_S15-PadB56)") (class "Default")
      (node (ref "U18") (pin "B56") (pinfunction "GP_Out_S15_B56") (pintype "passive"))
    )
    (net (code "196") (name "unconnected-(U18B-GP_Out_S16-PadB60)") (class "Default")
      (node (ref "U18") (pin "B60") (pinfunction "GP_Out_S16_B60") (pintype "passive"))
    )
    (net (code "197") (name "unconnected-(U18B-GP_Out_S17-PadB64)") (class "Default")
      (node (ref "U18") (pin "B64") (pinfunction "GP_Out_S17_B64") (pintype "passive"))
    )
    (net (code "198") (name "unconnected-(U18B-GP_Out_S18-PadB68)") (class "Default")
      (node (ref "U18") (pin "B68") (pinfunction "GP_Out_S18_B68") (pintype "passive"))
    )
    (net (code "199") (name "unconnected-(U18B-GP_Out_S19-PadB72)") (class "Default")
      (node (ref "U18") (pin "B72") (pinfunction "GP_Out_S19_B72") (pintype "passive"))
    )
    (net (code "200") (name "unconnected-(U18B-GP_Out_S20-PadB76)") (class "Default")
      (node (ref "U18") (pin "B76") (pinfunction "GP_Out_S20_B76") (pintype "passive"))
    )
    (net (code "201") (name "unconnected-(U18B-GP_Out_S21-PadB80)") (class "Default")
      (node (ref "U18") (pin "B80") (pinfunction "GP_Out_S21_B80") (pintype "passive"))
    )
    (net (code "202") (name "unconnected-(U18B-GP_Out_S22-PadB84)") (class "Default")
      (node (ref "U18") (pin "B84") (pinfunction "GP_Out_S22_B84") (pintype "passive"))
    )
    (net (code "203") (name "unconnected-(U18B-GP_Out_S23-PadB88)") (class "Default")
      (node (ref "U18") (pin "B88") (pinfunction "GP_Out_S23_B88") (pintype "passive"))
    )
    (net (code "204") (name "unconnected-(U18B-GP_Out_S24-PadB92)") (class "Default")
      (node (ref "U18") (pin "B92") (pinfunction "GP_Out_S24_B92") (pintype "passive"))
    )
    (net (code "205") (name "unconnected-(U18B-GP_Out_S25-PadB96)") (class "Default")
      (node (ref "U18") (pin "B96") (pinfunction "GP_Out_S25_B96") (pintype "passive"))
    )
    (net (code "206") (name "unconnected-(U18B-GP_Out_S26-PadB100)") (class "Default")
      (node (ref "U18") (pin "B100") (pinfunction "GP_Out_S26_B100") (pintype "passive"))
    )
    (net (code "207") (name "unconnected-(U18B-GP_Out_S27-PadB104)") (class "Default")
      (node (ref "U18") (pin "B104") (pinfunction "GP_Out_S27_B104") (pintype "passive"))
    )
    (net (code "208") (name "unconnected-(U18B-GP_Out_S28-PadB108)") (class "Default")
      (node (ref "U18") (pin "B108") (pinfunction "GP_Out_S28_B108") (pintype "passive"))
    )
    (net (code "209") (name "unconnected-(U18B-GP_Out_S29-PadB112)") (class "Default")
      (node (ref "U18") (pin "B112") (pinfunction "GP_Out_S29_B112") (pintype "passive"))
    )
    (net (code "210") (name "unconnected-(U18B-GP_Out_S30-PadB116)") (class "Default")
      (node (ref "U18") (pin "B116") (pinfunction "GP_Out_S30_B116") (pintype "passive"))
    )
    (net (code "211") (name "unconnected-(U18B-GP_Out_S31-PadB120)") (class "Default")
      (node (ref "U18") (pin "B120") (pinfunction "GP_Out_S31_B120") (pintype "passive"))
    )
    (net (code "212") (name "unconnected-(U18B-HomeCom-PadB9)") (class "Default")
      (node (ref "U18") (pin "B9") (pinfunction "HomeCom_B9") (pintype "passive"))
    )
    (net (code "213") (name "unconnected-(U18B-NegLimt4-PadB21)") (class "Default")
      (node (ref "U18") (pin "B21") (pinfunction "NegLimt4_B21") (pintype "passive"))
    )
    (net (code "214") (name "unconnected-(U18B-Opto_Input1-PadB59)") (class "Default")
      (node (ref "U18") (pin "B59") (pinfunction "Opto_Input1_B59") (pintype "passive"))
    )
    (net (code "215") (name "unconnected-(U18B-Opto_Input2-PadB61)") (class "Default")
      (node (ref "U18") (pin "B61") (pinfunction "Opto_Input2_B61") (pintype "passive"))
    )
    (net (code "216") (name "unconnected-(U18B-Opto_Input3-PadB63)") (class "Default")
      (node (ref "U18") (pin "B63") (pinfunction "Opto_Input3_B63") (pintype "passive"))
    )
    (net (code "217") (name "unconnected-(U18B-Opto_Input4-PadB73)") (class "Default")
      (node (ref "U18") (pin "B73") (pinfunction "Opto_Input4_B73") (pintype "passive"))
    )
    (net (code "218") (name "unconnected-(U18B-Opto_Input5-PadB75)") (class "Default")
      (node (ref "U18") (pin "B75") (pinfunction "Opto_Input5_B75") (pintype "passive"))
    )
    (net (code "219") (name "unconnected-(U18B-Opto_Input6-PadB77)") (class "Default")
      (node (ref "U18") (pin "B77") (pinfunction "Opto_Input6_B77") (pintype "passive"))
    )
    (net (code "220") (name "unconnected-(U18B-Opto_Input7-PadB79)") (class "Default")
      (node (ref "U18") (pin "B79") (pinfunction "Opto_Input7_B79") (pintype "passive"))
    )
    (net (code "221") (name "unconnected-(U18B-Opto_Input8-PadB83)") (class "Default")
      (node (ref "U18") (pin "B83") (pinfunction "Opto_Input8_B83") (pintype "passive"))
    )
    (net (code "222") (name "unconnected-(U18B-Opto_Input9-PadB85)") (class "Default")
      (node (ref "U18") (pin "B85") (pinfunction "Opto_Input9_B85") (pintype "passive"))
    )
    (net (code "223") (name "unconnected-(U18B-Opto_Input10-PadB87)") (class "Default")
      (node (ref "U18") (pin "B87") (pinfunction "Opto_Input10_B87") (pintype "passive"))
    )
    (net (code "224") (name "unconnected-(U18B-Opto_Input11-PadB89)") (class "Default")
      (node (ref "U18") (pin "B89") (pinfunction "Opto_Input11_B89") (pintype "passive"))
    )
    (net (code "225") (name "unconnected-(U18B-Opto_Input12-PadB93)") (class "Default")
      (node (ref "U18") (pin "B93") (pinfunction "Opto_Input12_B93") (pintype "passive"))
    )
    (net (code "226") (name "unconnected-(U18B-Opto_Input13-PadB95)") (class "Default")
      (node (ref "U18") (pin "B95") (pinfunction "Opto_Input13_B95") (pintype "passive"))
    )
    (net (code "227") (name "unconnected-(U18B-Opto_Input14-PadB97)") (class "Default")
      (node (ref "U18") (pin "B97") (pinfunction "Opto_Input14_B97") (pintype "passive"))
    )
    (net (code "228") (name "unconnected-(U18B-Opto_Input15-PadB99)") (class "Default")
      (node (ref "U18") (pin "B99") (pinfunction "Opto_Input15_B99") (pintype "passive"))
    )
    (net (code "229") (name "unconnected-(U18B-Opto_Input16-PadB103)") (class "Default")
      (node (ref "U18") (pin "B103") (pinfunction "Opto_Input16_B103") (pintype "passive"))
    )
    (net (code "230") (name "unconnected-(U18B-Opto_Input17-PadB105)") (class "Default")
      (node (ref "U18") (pin "B105") (pinfunction "Opto_Input17_B105") (pintype "passive"))
    )
    (net (code "231") (name "unconnected-(U18B-Opto_Input18-PadB107)") (class "Default")
      (node (ref "U18") (pin "B107") (pinfunction "Opto_Input18_B107") (pintype "passive"))
    )
    (net (code "232") (name "unconnected-(U18B-Opto_Input19-PadB109)") (class "Default")
      (node (ref "U18") (pin "B109") (pinfunction "Opto_Input19_B109") (pintype "passive"))
    )
    (net (code "233") (name "unconnected-(U18B-Opto_Input20-PadB113)") (class "Default")
      (node (ref "U18") (pin "B113") (pinfunction "Opto_Input20_B113") (pintype "passive"))
    )
    (net (code "234") (name "unconnected-(U18B-Opto_Input21-PadB115)") (class "Default")
      (node (ref "U18") (pin "B115") (pinfunction "Opto_Input21_B115") (pintype "passive"))
    )
    (net (code "235") (name "unconnected-(U18B-Opto_Input22-PadB117)") (class "Default")
      (node (ref "U18") (pin "B117") (pinfunction "Opto_Input22_B117") (pintype "passive"))
    )
    (net (code "236") (name "unconnected-(U18B-Opto_Input23-PadB119)") (class "Default")
      (node (ref "U18") (pin "B119") (pinfunction "Opto_Input23_B119") (pintype "passive"))
    )
    (net (code "237") (name "unconnected-(U18B-Opto_Input_Com1-PadB71)") (class "Default")
      (node (ref "U18") (pin "B71") (pinfunction "Opto_Input_Com1_B71") (pintype "passive"))
    )
    (net (code "238") (name "unconnected-(U18B-Opto_Input_Com2-PadB81)") (class "Default")
      (node (ref "U18") (pin "B81") (pinfunction "Opto_Input_Com2_B81") (pintype "passive"))
    )
    (net (code "239") (name "unconnected-(U18B-Opto_Input_Com3-PadB91)") (class "Default")
      (node (ref "U18") (pin "B91") (pinfunction "Opto_Input_Com3_B91") (pintype "passive"))
    )
    (net (code "240") (name "unconnected-(U18B-Opto_Input_Com4-PadB101)") (class "Default")
      (node (ref "U18") (pin "B101") (pinfunction "Opto_Input_Com4_B101") (pintype "passive"))
    )
    (net (code "241") (name "unconnected-(U18B-Opto_Input_Com5-PadB111)") (class "Default")
      (node (ref "U18") (pin "B111") (pinfunction "Opto_Input_Com5_B111") (pintype "passive"))
    )
    (net (code "242") (name "unconnected-(U18B-PosLimt4-PadB11)") (class "Default")
      (node (ref "U18") (pin "B11") (pinfunction "PosLimt4_B11") (pintype "passive"))
    )
    (net (code "243") (name "unconnected-(U18B-Step4-PadB37)") (class "Default")
      (node (ref "U18") (pin "B37") (pinfunction "Step4_B37") (pintype "passive"))
    )
    (net (code "244") (name "unconnected-(U18B-~Home1-PadB7)") (class "Default")
      (node (ref "U18") (pin "B7") (pinfunction "~Home1_B7") (pintype "passive"))
    )
    (net (code "245") (name "unconnected-(U18B-~Home2-PadB5)") (class "Default")
      (node (ref "U18") (pin "B5") (pinfunction "~Home2_B5") (pintype "passive"))
    )
    (net (code "246") (name "unconnected-(U18B-~Home3-PadB3)") (class "Default")
      (node (ref "U18") (pin "B3") (pinfunction "~Home3_B3") (pintype "passive"))
    )
    (net (code "247") (name "unconnected-(U18B-~Home4-PadB1)") (class "Default")
      (node (ref "U18") (pin "B1") (pinfunction "~Home4_B1") (pintype "passive"))
    )
  )
)
